# design.net
KiCad netlist of a schematic drawn in Altium Designer
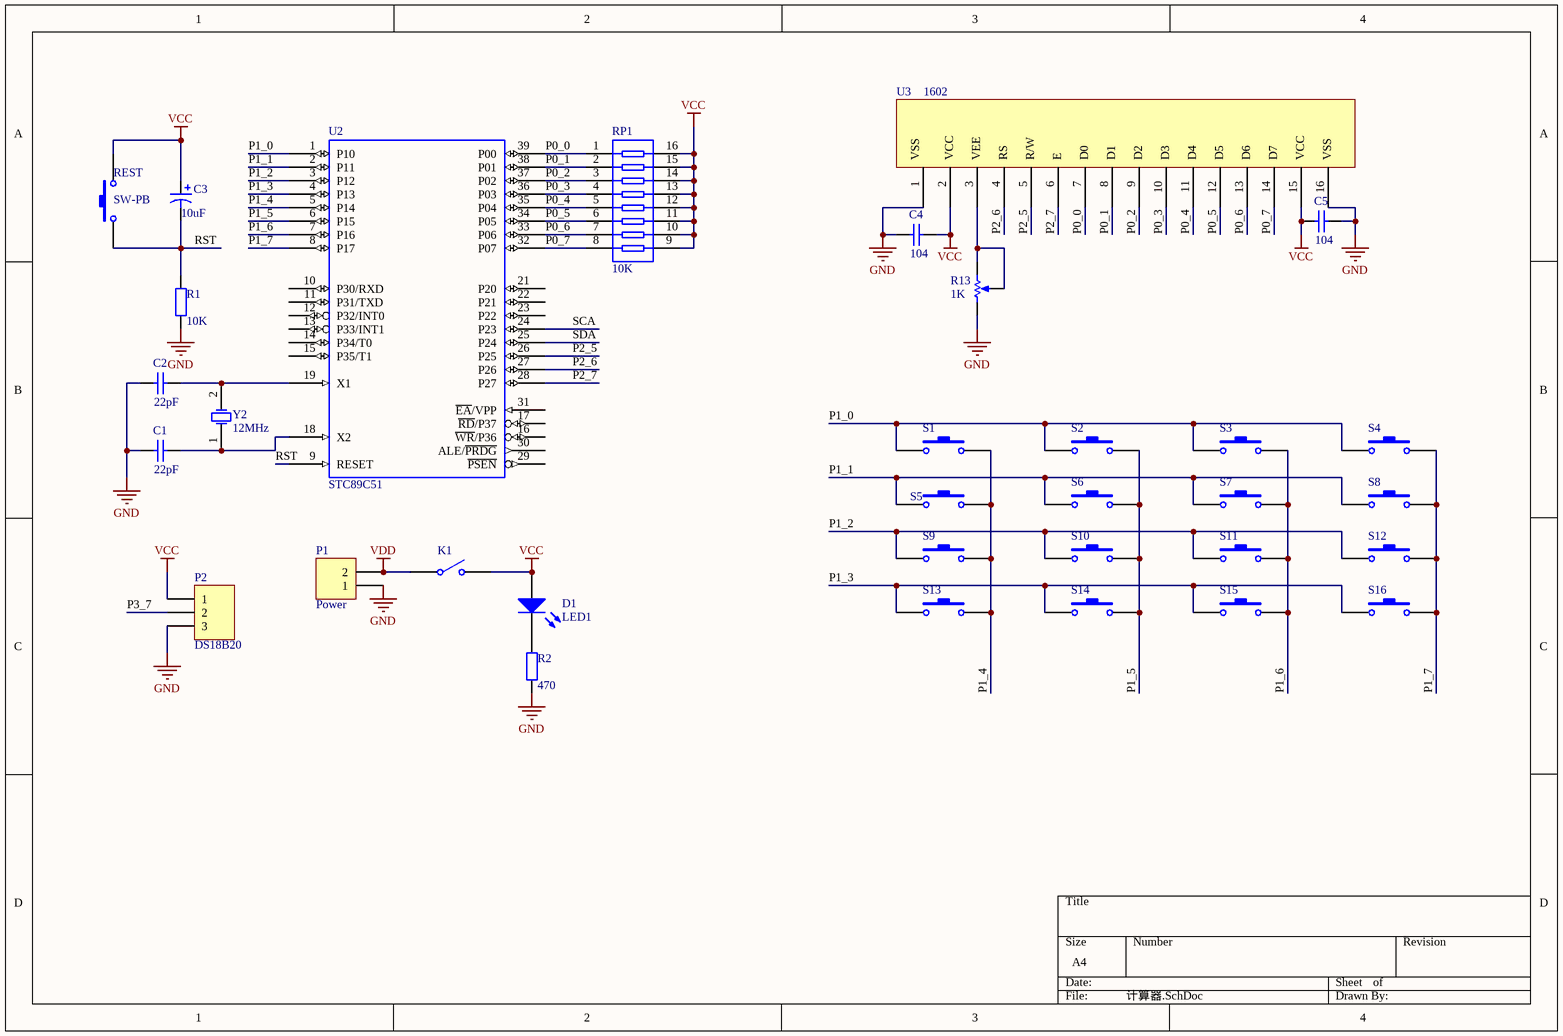
[diagram p0: 计算器.SchDoc]

(export (version "E")
  (design (tool "Eeschema 10.0.6"))
  (components
    (comp (ref "C1")
      (value "22pF")
      (footprint "RAD-0.3")
      (description "Capacitor")
      (fields (field (name "PUBLISHER") "Altium Limited"))
      (libsource (lib "Miscellaneous Devices") (part "Cap"))
    )
    (comp (ref "C2")
      (value "22pF")
      (footprint "RAD-0.3")
      (description "Capacitor")
      (fields (field (name "PUBLISHER") "Altium Limited"))
      (libsource (lib "Miscellaneous Devices") (part "Cap"))
    )
    (comp (ref "C3")
      (value "10uF")
      (footprint "RB7.6-15")
      (description "Polarized Capacitor (Radial)")
      (fields (field (name "PUBLISHER") "Altium Limited"))
      (libsource (lib "Miscellaneous Devices") (part "Cap Pol1"))
    )
    (comp (ref "C4")
      (value "104")
      (footprint "RAD-0.3")
      (description "Capacitor")
      (fields (field (name "PUBLISHER") "Altium Limited"))
      (libsource (lib "Miscellaneous Devices") (part "Cap"))
    )
    (comp (ref "C5")
      (value "104")
      (footprint "RAD-0.3")
      (description "Capacitor")
      (fields (field (name "PUBLISHER") "Altium Limited"))
      (libsource (lib "Miscellaneous Devices") (part "Cap"))
    )
    (comp (ref "D1")
      (value "LED1")
      (footprint "LED-1")
      (description "Typical RED GaAs LED")
      (fields (field (name "PUBLISHER") "Altium Limited"))
      (libsource (lib "Miscellaneous Devices") (part "LED1"))
    )
    (comp (ref "K1")
      (value "~")
      (footprint "SPST-2")
      (description "Single-Pole, Single-Throw Switch")
      (fields (field (name "PUBLISHER") "Altium Limited"))
      (libsource (lib "Miscellaneous Devices") (part "SW-SPST"))
    )
    (comp (ref "P1")
      (value "Power")
      (footprint "HDR1X2")
      (description "Header, 2-Pin")
      (fields (field (name "PUBLISHER") "Altium Limited"))
      (libsource (lib "Miscellaneous Connectors") (part "Header 2"))
    )
    (comp (ref "P2")
      (value "DS18B20")
      (footprint "HDR1X3")
      (description "Header, 3-Pin")
      (fields (field (name "PUBLISHER") "Altium Limited"))
      (libsource (lib "Miscellaneous Connectors") (part "Header 3"))
    )
    (comp (ref "R1")
      (value "10K")
      (footprint "AXIAL-0.4")
      (description "Resistor")
      (fields (field (name "PUBLISHER") "Altium Limited"))
      (libsource (lib "Miscellaneous Devices") (part "Res2"))
    )
    (comp (ref "R2")
      (value "470")
      (footprint "AXIAL-0.4")
      (description "Resistor")
      (fields (field (name "PUBLISHER") "Altium Limited"))
      (libsource (lib "Miscellaneous Devices") (part "Res2"))
    )
    (comp (ref "R13")
      (value "1K")
      (footprint "VR5")
      (description "Potentiometer")
      (fields (field (name "PUBLISHER") "Altium Limited"))
      (libsource (lib "Miscellaneous Devices") (part "RPot"))
    )
    (comp (ref "REST")
      (value "SW-PB")
      (footprint "SPST-2")
      (description "Switch")
      (fields (field (name "PUBLISHER") "Altium Limited"))
      (libsource (lib "Miscellaneous Devices") (part "SW-PB"))
    )
    (comp (ref "RP1") (value "10K") (footprint "DIP16") (libsource (lib "电阻") (part "RESPACK4")))
    (comp (ref "S1")
      (value "~")
      (footprint "SPST-2")
      (description "Switch")
      (fields (field (name "PUBLISHER") "Altium Limited"))
      (libsource (lib "Miscellaneous Devices") (part "SW-PB"))
    )
    (comp (ref "S2")
      (value "~")
      (footprint "SPST-2")
      (description "Switch")
      (fields (field (name "PUBLISHER") "Altium Limited"))
      (libsource (lib "Miscellaneous Devices") (part "SW-PB"))
    )
    (comp (ref "S3")
      (value "~")
      (footprint "SPST-2")
      (description "Switch")
      (fields (field (name "PUBLISHER") "Altium Limited"))
      (libsource (lib "Miscellaneous Devices") (part "SW-PB"))
    )
    (comp (ref "S4")
      (value "~")
      (footprint "SPST-2")
      (description "Switch")
      (fields (field (name "PUBLISHER") "Altium Limited"))
      (libsource (lib "Miscellaneous Devices") (part "SW-PB"))
    )
    (comp (ref "S5")
      (value "~")
      (footprint "SPST-2")
      (description "Switch")
      (fields (field (name "PUBLISHER") "Altium Limited"))
      (libsource (lib "Miscellaneous Devices") (part "SW-PB"))
    )
    (comp (ref "S6")
      (value "~")
      (footprint "SPST-2")
      (description "Switch")
      (fields (field (name "PUBLISHER") "Altium Limited"))
      (libsource (lib "Miscellaneous Devices") (part "SW-PB"))
    )
    (comp (ref "S7")
      (value "~")
      (footprint "SPST-2")
      (description "Switch")
      (fields (field (name "PUBLISHER") "Altium Limited"))
      (libsource (lib "Miscellaneous Devices") (part "SW-PB"))
    )
    (comp (ref "S8")
      (value "~")
      (footprint "SPST-2")
      (description "Switch")
      (fields (field (name "PUBLISHER") "Altium Limited"))
      (libsource (lib "Miscellaneous Devices") (part "SW-PB"))
    )
    (comp (ref "S9")
      (value "~")
      (footprint "SPST-2")
      (description "Switch")
      (fields (field (name "PUBLISHER") "Altium Limited"))
      (libsource (lib "Miscellaneous Devices") (part "SW-PB"))
    )
    (comp (ref "S10")
      (value "~")
      (footprint "SPST-2")
      (description "Switch")
      (fields (field (name "PUBLISHER") "Altium Limited"))
      (libsource (lib "Miscellaneous Devices") (part "SW-PB"))
    )
    (comp (ref "S11")
      (value "~")
      (footprint "SPST-2")
      (description "Switch")
      (fields (field (name "PUBLISHER") "Altium Limited"))
      (libsource (lib "Miscellaneous Devices") (part "SW-PB"))
    )
    (comp (ref "S12")
      (value "~")
      (footprint "SPST-2")
      (description "Switch")
      (fields (field (name "PUBLISHER") "Altium Limited"))
      (libsource (lib "Miscellaneous Devices") (part "SW-PB"))
    )
    (comp (ref "S13")
      (value "~")
      (footprint "SPST-2")
      (description "Switch")
      (fields (field (name "PUBLISHER") "Altium Limited"))
      (libsource (lib "Miscellaneous Devices") (part "SW-PB"))
    )
    (comp (ref "S14")
      (value "~")
      (footprint "SPST-2")
      (description "Switch")
      (fields (field (name "PUBLISHER") "Altium Limited"))
      (libsource (lib "Miscellaneous Devices") (part "SW-PB"))
    )
    (comp (ref "S15")
      (value "~")
      (footprint "SPST-2")
      (description "Switch")
      (fields (field (name "PUBLISHER") "Altium Limited"))
      (libsource (lib "Miscellaneous Devices") (part "SW-PB"))
    )
    (comp (ref "S16")
      (value "~")
      (footprint "SPST-2")
      (description "Switch")
      (fields (field (name "PUBLISHER") "Altium Limited"))
      (libsource (lib "Miscellaneous Devices") (part "SW-PB"))
    )
    (comp (ref "U2") (value "STC89C51") (libsource (lib "单片机及相关") (part "AT89C51")))
    (comp (ref "U3") (value "1602") (libsource (lib "signal general") (part "1602")))
    (comp (ref "Y2")
      (value "12MHz")
      (footprint "BCY-W2/D3.1")
      (description "Crystal Oscillator")
      (fields (field (name "PUBLISHER") "Altium Limited"))
      (libsource (lib "Miscellaneous Devices") (part "XTAL"))
    )
  )
  (nets
    (net (code "1") (name "/P0_0") (class "Default")
      (node (ref "RP1") (pin "1") (pinfunction "1_1") (pintype "passive"))
      (node (ref "U2") (pin "39") (pinfunction "P00_39") (pintype "bidirectional"))
      (node (ref "U3") (pin "7") (pintype "passive"))
    )
    (net (code "2") (name "/P0_1") (class "Default")
      (node (ref "RP1") (pin "2") (pinfunction "2_2") (pintype "passive"))
      (node (ref "U2") (pin "38") (pinfunction "P01_38") (pintype "bidirectional"))
      (node (ref "U3") (pin "8") (pintype "passive"))
    )
    (net (code "3") (name "/P0_2") (class "Default")
      (node (ref "RP1") (pin "3") (pinfunction "3_3") (pintype "passive"))
      (node (ref "U2") (pin "37") (pinfunction "P02_37") (pintype "bidirectional"))
      (node (ref "U3") (pin "9") (pintype "passive"))
    )
    (net (code "4") (name "/P0_3") (class "Default")
      (node (ref "RP1") (pin "4") (pinfunction "4_4") (pintype "passive"))
      (node (ref "U2") (pin "36") (pinfunction "P03_36") (pintype "bidirectional"))
      (node (ref "U3") (pin "10") (pintype "passive"))
    )
    (net (code "5") (name "/P0_4") (class "Default")
      (node (ref "RP1") (pin "5") (pinfunction "5_5") (pintype "passive"))
      (node (ref "U2") (pin "35") (pinfunction "P04_35") (pintype "bidirectional"))
      (node (ref "U3") (pin "11") (pintype "passive"))
    )
    (net (code "6") (name "/P0_5") (class "Default")
      (node (ref "RP1") (pin "6") (pinfunction "6_6") (pintype "passive"))
      (node (ref "U2") (pin "34") (pinfunction "P05_34") (pintype "bidirectional"))
      (node (ref "U3") (pin "12") (pintype "passive"))
    )
    (net (code "7") (name "/P0_6") (class "Default")
      (node (ref "RP1") (pin "7") (pinfunction "7_7") (pintype "passive"))
      (node (ref "U2") (pin "33") (pinfunction "P06_33") (pintype "bidirectional"))
    )
    (net (code "8") (name "/P0_7") (class "Default")
      (node (ref "RP1") (pin "8") (pinfunction "8_8") (pintype "passive"))
      (node (ref "U2") (pin "32") (pinfunction "P07_32") (pintype "bidirectional"))
    )
    (net (code "9") (name "/P1_0") (class "Default")
      (node (ref "S1") (pin "1") (pinfunction "1_1") (pintype "passive"))
      (node (ref "S2") (pin "1") (pinfunction "1_1") (pintype "passive"))
      (node (ref "S3") (pin "1") (pinfunction "1_1") (pintype "passive"))
      (node (ref "S4") (pin "1") (pinfunction "1_1") (pintype "passive"))
      (node (ref "U2") (pin "1") (pinfunction "P10_1") (pintype "bidirectional"))
    )
    (net (code "10") (name "/P1_1") (class "Default")
      (node (ref "S5") (pin "1") (pinfunction "1_1") (pintype "passive"))
      (node (ref "S6") (pin "1") (pinfunction "1_1") (pintype "passive"))
      (node (ref "S7") (pin "1") (pinfunction "1_1") (pintype "passive"))
      (node (ref "S8") (pin "1") (pinfunction "1_1") (pintype "passive"))
      (node (ref "U2") (pin "2") (pinfunction "P11_2") (pintype "bidirectional"))
    )
    (net (code "11") (name "/P1_2") (class "Default")
      (node (ref "S10") (pin "1") (pinfunction "1_1") (pintype "passive"))
      (node (ref "S11") (pin "1") (pinfunction "1_1") (pintype "passive"))
      (node (ref "S12") (pin "1") (pinfunction "1_1") (pintype "passive"))
      (node (ref "S9") (pin "1") (pinfunction "1_1") (pintype "passive"))
      (node (ref "U2") (pin "3") (pinfunction "P12_3") (pintype "bidirectional"))
    )
    (net (code "12") (name "/P1_3") (class "Default")
      (node (ref "S13") (pin "1") (pinfunction "1_1") (pintype "passive"))
      (node (ref "S14") (pin "1") (pinfunction "1_1") (pintype "passive"))
      (node (ref "S15") (pin "1") (pinfunction "1_1") (pintype "passive"))
      (node (ref "S16") (pin "1") (pinfunction "1_1") (pintype "passive"))
      (node (ref "U2") (pin "4") (pinfunction "P13_4") (pintype "bidirectional"))
    )
    (net (code "13") (name "/P1_4") (class "Default")
      (node (ref "S1") (pin "2") (pinfunction "2_2") (pintype "passive"))
      (node (ref "S13") (pin "2") (pinfunction "2_2") (pintype "passive"))
      (node (ref "S5") (pin "2") (pinfunction "2_2") (pintype "passive"))
      (node (ref "S9") (pin "2") (pinfunction "2_2") (pintype "passive"))
      (node (ref "U2") (pin "5") (pinfunction "P14_5") (pintype "bidirectional"))
    )
    (net (code "14") (name "/P1_5") (class "Default")
      (node (ref "S10") (pin "2") (pinfunction "2_2") (pintype "passive"))
      (node (ref "S14") (pin "2") (pinfunction "2_2") (pintype "passive"))
      (node (ref "S2") (pin "2") (pinfunction "2_2") (pintype "passive"))
      (node (ref "S6") (pin "2") (pinfunction "2_2") (pintype "passive"))
      (node (ref "U2") (pin "6") (pinfunction "P15_6") (pintype "bidirectional"))
    )
    (net (code "15") (name "/P1_6") (class "Default")
      (node (ref "S11") (pin "2") (pinfunction "2_2") (pintype "passive"))
      (node (ref "S15") (pin "2") (pinfunction "2_2") (pintype "passive"))
      (node (ref "S3") (pin "2") (pinfunction "2_2") (pintype "passive"))
      (node (ref "S7") (pin "2") (pinfunction "2_2") (pintype "passive"))
      (node (ref "U2") (pin "7") (pinfunction "P16_7") (pintype "bidirectional"))
    )
    (net (code "16") (name "/P1_7") (class "Default")
      (node (ref "S12") (pin "2") (pinfunction "2_2") (pintype "passive"))
      (node (ref "S16") (pin "2") (pinfunction "2_2") (pintype "passive"))
      (node (ref "S4") (pin "2") (pinfunction "2_2") (pintype "passive"))
      (node (ref "S8") (pin "2") (pinfunction "2_2") (pintype "passive"))
      (node (ref "U2") (pin "8") (pinfunction "P17_8") (pintype "bidirectional"))
    )
    (net (code "17") (name "/P2_5") (class "Default")
      (node (ref "U2") (pin "26") (pinfunction "P25_26") (pintype "bidirectional"))
    )
    (net (code "18") (name "/P2_6") (class "Default")
      (node (ref "U2") (pin "27") (pinfunction "P26_27") (pintype "bidirectional"))
    )
    (net (code "19") (name "/P2_7") (class "Default")
      (node (ref "U2") (pin "28") (pinfunction "P27_28") (pintype "bidirectional"))
    )
    (net (code "20") (name "/P3_7") (class "Default")
      (node (ref "P2") (pin "2") (pinfunction "2_2") (pintype "passive"))
    )
    (net (code "21") (name "/RST") (class "Default")
      (node (ref "C3") (pin "2") (pinfunction "2_2") (pintype "passive"))
      (node (ref "R1") (pin "2") (pinfunction "2_2") (pintype "passive"))
      (node (ref "REST") (pin "1") (pinfunction "1_1") (pintype "passive"))
      (node (ref "U2") (pin "9") (pinfunction "RESET_9") (pintype "input"))
    )
    (net (code "22") (name "/SCA") (class "Default")
      (node (ref "U2") (pin "24") (pinfunction "P23_24") (pintype "bidirectional"))
    )
    (net (code "23") (name "/SDA") (class "Default")
      (node (ref "U2") (pin "25") (pinfunction "P24_25") (pintype "bidirectional"))
    )
    (net (code "24") (name "GND") (class "Default")
      (node (ref "C1") (pin "1") (pinfunction "1_1") (pintype "passive"))
      (node (ref "C2") (pin "1") (pinfunction "1_1") (pintype "passive"))
      (node (ref "C4") (pin "1") (pinfunction "1_1") (pintype "passive"))
      (node (ref "C5") (pin "2") (pinfunction "2_2") (pintype "passive"))
      (node (ref "P1") (pin "1") (pinfunction "1_1") (pintype "passive"))
      (node (ref "P2") (pin "3") (pinfunction "3_3") (pintype "passive"))
      (node (ref "R1") (pin "1") (pinfunction "1_1") (pintype "passive"))
      (node (ref "R13") (pin "1") (pinfunction "TOP_1") (pintype "passive"))
      (node (ref "R2") (pin "1") (pinfunction "1_1") (pintype "passive"))
      (node (ref "U2") (pin "20") (pinfunction "GND_20") (pintype "power_in"))
      (node (ref "U3") (pin "1") (pintype "passive"))
      (node (ref "U3") (pin "16") (pintype "passive"))
    )
    (net (code "25") (name "Net-(D1-K)") (class "Default")
      (node (ref "D1") (pin "2") (pinfunction "K_2") (pintype "passive"))
      (node (ref "R2") (pin "2") (pinfunction "2_2") (pintype "passive"))
    )
    (net (code "26") (name "Net-(R13-BOT)") (class "Default")
      (node (ref "R13") (pin "2") (pinfunction "BOT_2") (pintype "passive"))
      (node (ref "R13") (pin "3") (pinfunction "TAP_3") (pintype "passive"))
      (node (ref "U3") (pin "3") (pintype "passive"))
    )
    (net (code "27") (name "Net-(U2-X1)") (class "Default")
      (node (ref "C2") (pin "2") (pinfunction "2_2") (pintype "passive"))
      (node (ref "U2") (pin "19") (pinfunction "X1_19") (pintype "input"))
      (node (ref "Y2") (pin "2") (pinfunction "OSC2_2") (pintype "passive"))
    )
    (net (code "28") (name "Net-(U2-X2)") (class "Default")
      (node (ref "C1") (pin "2") (pinfunction "2_2") (pintype "passive"))
      (node (ref "U2") (pin "18") (pinfunction "X2_18") (pintype "input"))
      (node (ref "Y2") (pin "1") (pinfunction "OSC1_1") (pintype "passive"))
    )
    (net (code "29") (name "VCC") (class "Default")
      (node (ref "C3") (pin "1") (pinfunction "1_1") (pintype "passive"))
      (node (ref "C4") (pin "2") (pinfunction "2_2") (pintype "passive"))
      (node (ref "C5") (pin "1") (pinfunction "1_1") (pintype "passive"))
      (node (ref "D1") (pin "1") (pinfunction "A_1") (pintype "passive"))
      (node (ref "K1") (pin "2") (pinfunction "NO_2") (pintype "passive"))
      (node (ref "P2") (pin "1") (pinfunction "1_1") (pintype "passive"))
      (node (ref "REST") (pin "2") (pinfunction "2_2") (pintype "passive"))
      (node (ref "RP1") (pin "10") (pinfunction "10_10") (pintype "passive"))
      (node (ref "RP1") (pin "11") (pinfunction "11_11") (pintype "passive"))
      (node (ref "RP1") (pin "12") (pinfunction "12_12") (pintype "passive"))
      (node (ref "RP1") (pin "13") (pinfunction "13_13") (pintype "passive"))
      (node (ref "RP1") (pin "14") (pinfunction "14_14") (pintype "passive"))
      (node (ref "RP1") (pin "15") (pinfunction "15_15") (pintype "passive"))
      (node (ref "RP1") (pin "16") (pinfunction "16_16") (pintype "passive"))
      (node (ref "RP1") (pin "9") (pinfunction "9_9") (pintype "passive"))
      (node (ref "U2") (pin "40") (pinfunction "VCC_40") (pintype "power_in"))
      (node (ref "U3") (pin "15") (pintype "passive"))
      (node (ref "U3") (pin "2") (pintype "passive"))
    )
    (net (code "30") (name "VDD") (class "Default")
      (node (ref "K1") (pin "1") (pinfunction "COMMON_1") (pintype "passive"))
      (node (ref "P1") (pin "2") (pinfunction "2_2") (pintype "passive"))
    )
    (net (code "31") (name "unconnected-(U2-ALE{slash}~{PRDG}-Pad30)") (class "Default")
      (node (ref "U2") (pin "30") (pinfunction "ALE/~{PRDG}_30") (pintype "output"))
    )
    (net (code "32") (name "unconnected-(U2-P20-Pad21)") (class "Default")
      (node (ref "U2") (pin "21") (pinfunction "P20_21") (pintype "bidirectional"))
    )
    (net (code "33") (name "unconnected-(U2-P21-Pad22)") (class "Default")
      (node (ref "U2") (pin "22") (pinfunction "P21_22") (pintype "bidirectional"))
    )
    (net (code "34") (name "unconnected-(U2-P22-Pad23)") (class "Default")
      (node (ref "U2") (pin "23") (pinfunction "P22_23") (pintype "bidirectional"))
    )
    (net (code "35") (name "unconnected-(U2-P30{slash}RXD-Pad10)") (class "Default")
      (node (ref "U2") (pin "10") (pinfunction "P30/RXD_10") (pintype "bidirectional"))
    )
    (net (code "36") (name "unconnected-(U2-P31{slash}TXD-Pad11)") (class "Default")
      (node (ref "U2") (pin "11") (pinfunction "P31/TXD_11") (pintype "bidirectional"))
    )
    (net (code "37") (name "unconnected-(U2-P32{slash}INT0-Pad12)") (class "Default")
      (node (ref "U2") (pin "12") (pinfunction "P32/INT0_12") (pintype "bidirectional"))
    )
    (net (code "38") (name "unconnected-(U2-P33{slash}INT1-Pad13)") (class "Default")
      (node (ref "U2") (pin "13") (pinfunction "P33/INT1_13") (pintype "bidirectional"))
    )
    (net (code "39") (name "unconnected-(U2-P34{slash}T0-Pad14)") (class "Default")
      (node (ref "U2") (pin "14") (pinfunction "P34/T0_14") (pintype "bidirectional"))
    )
    (net (code "40") (name "unconnected-(U2-P35{slash}T1-Pad15)") (class "Default")
      (node (ref "U2") (pin "15") (pinfunction "P35/T1_15") (pintype "bidirectional"))
    )
    (net (code "41") (name "unconnected-(U2-~{EA}{slash}VPP-Pad31)") (class "Default")
      (node (ref "U2") (pin "31") (pinfunction "~{EA}/VPP_31") (pintype "input"))
    )
    (net (code "42") (name "unconnected-(U2-~{PSEN}-Pad29)") (class "Default")
      (node (ref "U2") (pin "29") (pinfunction "~{PSEN}_29") (pintype "output"))
    )
    (net (code "43") (name "unconnected-(U2-~{RD}{slash}P37-Pad17)") (class "Default")
      (node (ref "U2") (pin "17") (pinfunction "~{RD}/P37_17") (pintype "bidirectional"))
    )
    (net (code "44") (name "unconnected-(U2-~{WR}{slash}P36-Pad16)") (class "Default")
      (node (ref "U2") (pin "16") (pinfunction "~{WR}/P36_16") (pintype "bidirectional"))
    )
    (net (code "45") (name "unconnected-(U3-Pad4)") (class "Default")
      (node (ref "U3") (pin "4") (pintype "passive"))
    )
    (net (code "46") (name "unconnected-(U3-Pad5)") (class "Default")
      (node (ref "U3") (pin "5") (pintype "passive"))
    )
    (net (code "47") (name "unconnected-(U3-Pad6)") (class "Default")
      (node (ref "U3") (pin "6") (pintype "passive"))
    )
    (net (code "48") (name "unconnected-(U3-Pad13)") (class "Default")
      (node (ref "U3") (pin "13") (pintype "passive"))
    )
    (net (code "49") (name "unconnected-(U3-Pad14)") (class "Default")
      (node (ref "U3") (pin "14") (pintype "passive"))
    )
  )
)
